# connector_motor.net
KiCad netlist of a schematic drawn in EAGLE
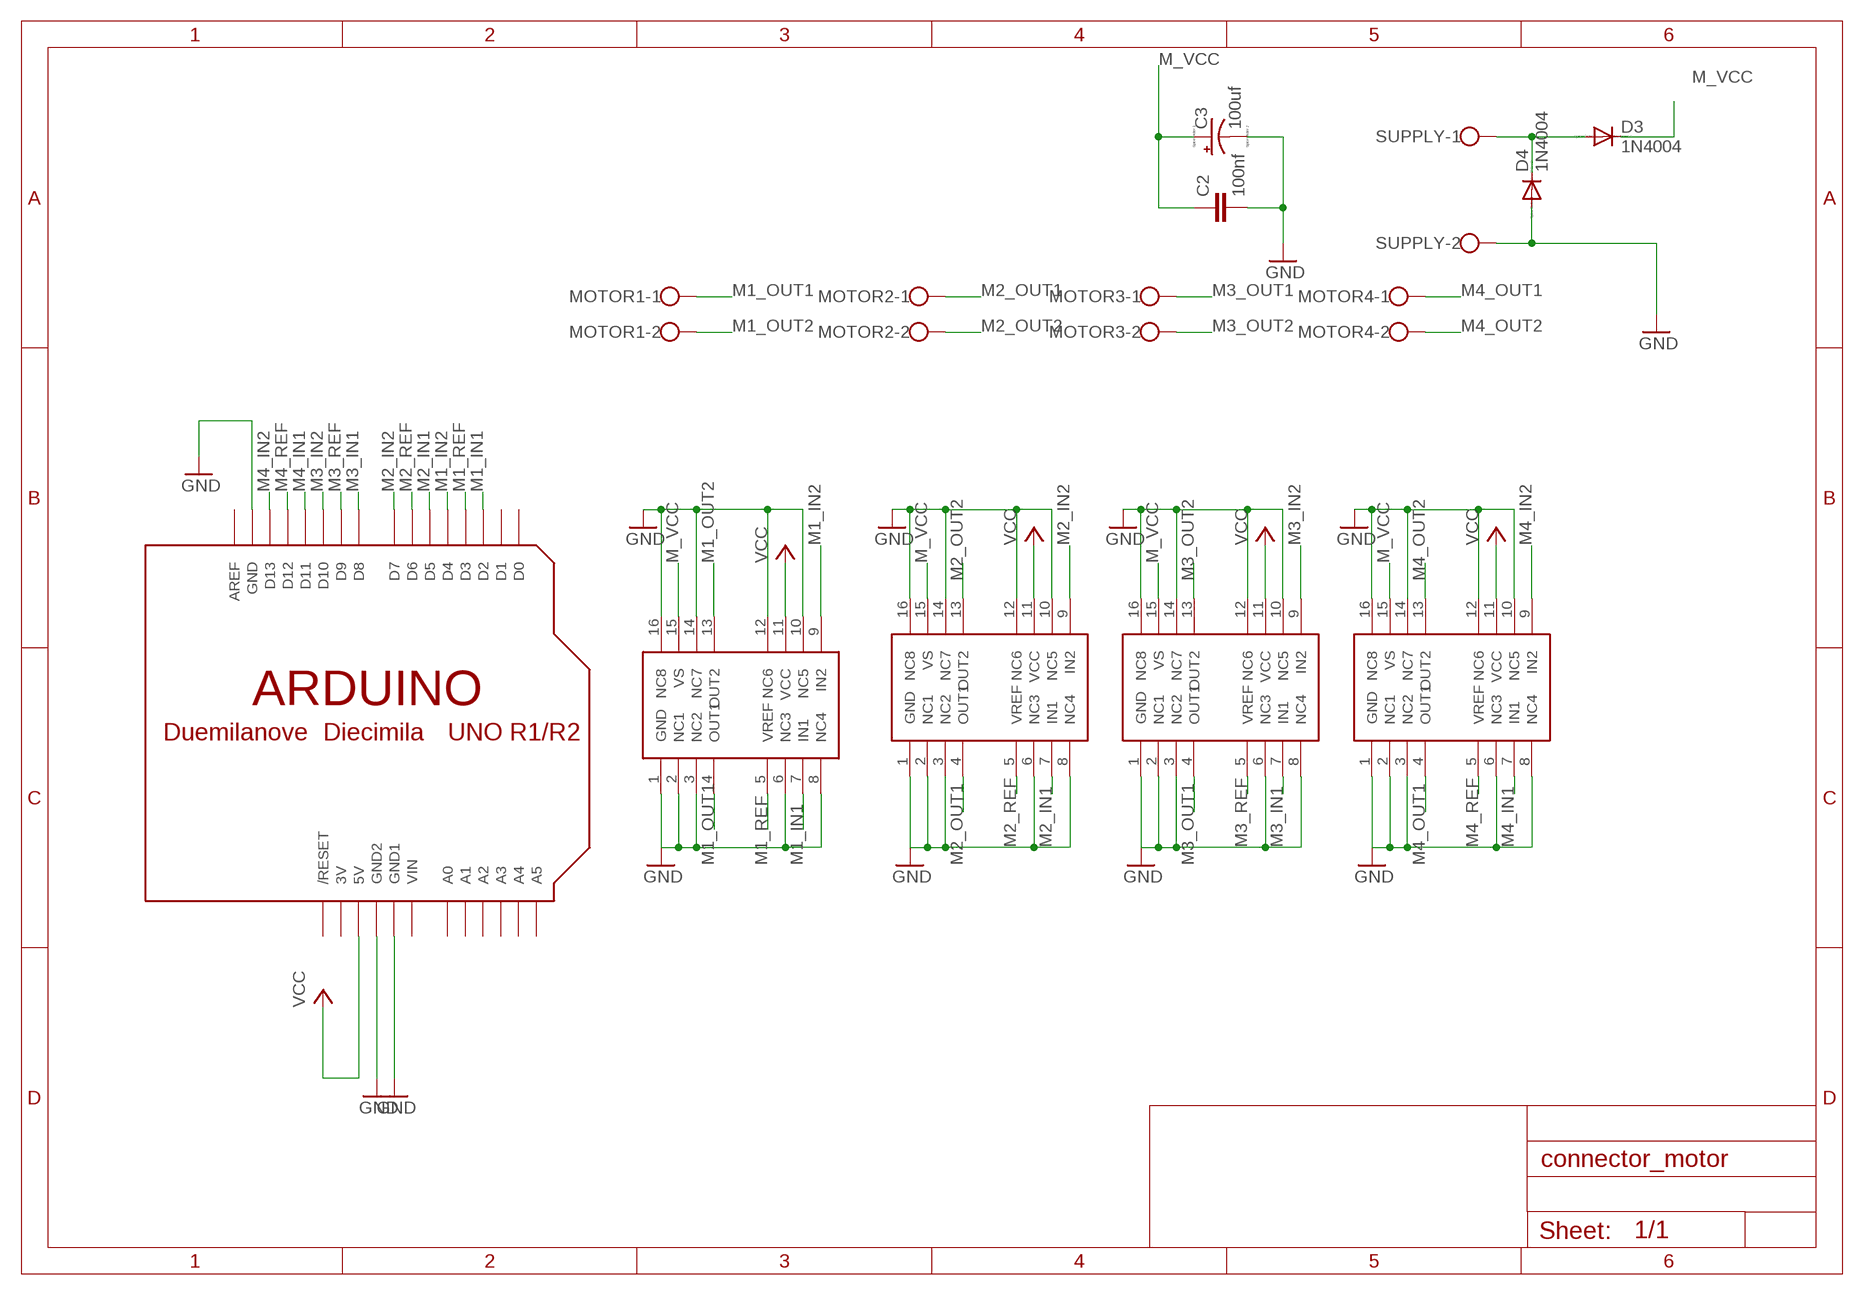
[diagram p0: schematic, sheet 1]

(export (version "E")
  (design (tool "Eeschema 10.0.6"))
  (components
    (comp (ref "C2")
      (value "100nf")
      (footprint "eagle-import:C0603")
      (libsource (lib "eagle-import") (part "C-EUC0603"))
    )
    (comp (ref "C3")
      (value "100uf")
      (footprint "eagle-import:153CLV-0405")
      (libsource (lib "eagle-import") (part "CPOL-US153CLV-0405"))
    )
    (comp (ref "D3")
      (value "1N4004")
      (footprint "eagle-import:DO41-10")
      (libsource (lib "eagle-import") (part "1N4004"))
    )
    (comp (ref "D4")
      (value "1N4004")
      (footprint "eagle-import:DO41-10")
      (libsource (lib "eagle-import") (part "1N4004"))
    )
    (comp (ref "MOTOR1")
      (value "W237-102")
      (footprint "eagle-import:W237-102")
      (fields (field (name "MPN") "237-102"))
      (libsource (lib "eagle-import") (part "W237-102"))
    )
    (comp (ref "MOTOR2")
      (value "W237-102")
      (footprint "eagle-import:W237-102")
      (fields (field (name "MPN") "237-102"))
      (libsource (lib "eagle-import") (part "W237-102"))
    )
    (comp (ref "MOTOR3")
      (value "W237-102")
      (footprint "eagle-import:W237-102")
      (fields (field (name "MPN") "237-102"))
      (libsource (lib "eagle-import") (part "W237-102"))
    )
    (comp (ref "MOTOR4")
      (value "W237-102")
      (footprint "eagle-import:W237-102")
      (fields (field (name "MPN") "237-102"))
      (libsource (lib "eagle-import") (part "W237-102"))
    )
    (comp (ref "SUPPLY")
      (value "W237-102")
      (footprint "eagle-import:W237-102")
      (fields (field (name "MPN") "237-102"))
      (libsource (lib "eagle-import") (part "W237-102"))
    )
    (comp (ref "U$1")
      (value "ARDUINO-NOHOLE")
      (footprint "eagle-import:ARDUINO-NOHOLE")
      (libsource (lib "eagle-import") (part "ARDUINO-NOHOLE"))
    )
    (comp (ref "U$2")
      (value "MOTOR-DRIVER-TA7281FG")
      (footprint "eagle-import:MOTOR-DRIVER-TA7291FG")
      (libsource (lib "eagle-import") (part "MOTOR-DRIVER-TA7281FG"))
    )
    (comp (ref "U$3")
      (value "MOTOR-DRIVER-TA7281FG")
      (footprint "eagle-import:MOTOR-DRIVER-TA7291FG")
      (libsource (lib "eagle-import") (part "MOTOR-DRIVER-TA7281FG"))
    )
    (comp (ref "U$4")
      (value "MOTOR-DRIVER-TA7281FG")
      (footprint "eagle-import:MOTOR-DRIVER-TA7291FG")
      (libsource (lib "eagle-import") (part "MOTOR-DRIVER-TA7281FG"))
    )
    (comp (ref "U$5")
      (value "MOTOR-DRIVER-TA7281FG")
      (footprint "eagle-import:MOTOR-DRIVER-TA7291FG")
      (libsource (lib "eagle-import") (part "MOTOR-DRIVER-TA7281FG"))
    )
  )
  (nets
    (net (code "1") (name "/3V") (class "Default")
      (node (ref "U$1") (pin "3V") (pinfunction "3V_3V") (pintype "power_in"))
    )
    (net (code "2") (name "/M1_IN1") (class "Default")
      (node (ref "U$1") (pin "D2") (pinfunction "D2_D2") (pintype "bidirectional"))
      (node (ref "U$3") (pin "7") (pinfunction "IN1_7") (pintype "bidirectional"))
    )
    (net (code "3") (name "/M1_IN2") (class "Default")
      (node (ref "U$1") (pin "D4") (pinfunction "D4_D4") (pintype "bidirectional"))
      (node (ref "U$3") (pin "9") (pinfunction "IN2_9") (pintype "bidirectional"))
    )
    (net (code "4") (name "/M1_OUT1") (class "Default")
      (node (ref "MOTOR1") (pin "1") (pinfunction "KL_1") (pintype "passive"))
      (node (ref "U$3") (pin "4") (pinfunction "OUT1_4") (pintype "bidirectional"))
    )
    (net (code "5") (name "/M1_OUT2") (class "Default")
      (node (ref "MOTOR1") (pin "2") (pinfunction "KL_2") (pintype "passive"))
      (node (ref "U$3") (pin "13") (pinfunction "OUT2_13") (pintype "bidirectional"))
    )
    (net (code "6") (name "/M1_REF") (class "Default")
      (node (ref "U$1") (pin "D3") (pinfunction "D3_D3") (pintype "bidirectional"))
      (node (ref "U$3") (pin "5") (pinfunction "VREF_5") (pintype "bidirectional"))
    )
    (net (code "7") (name "/M2_IN1") (class "Default")
      (node (ref "U$1") (pin "D5") (pinfunction "D5_D5") (pintype "bidirectional"))
      (node (ref "U$4") (pin "7") (pinfunction "IN1_7") (pintype "bidirectional"))
    )
    (net (code "8") (name "/M2_IN2") (class "Default")
      (node (ref "U$1") (pin "D7") (pinfunction "D7_D7") (pintype "bidirectional"))
      (node (ref "U$4") (pin "9") (pinfunction "IN2_9") (pintype "bidirectional"))
    )
    (net (code "9") (name "/M2_OUT1") (class "Default")
      (node (ref "MOTOR2") (pin "1") (pinfunction "KL_1") (pintype "passive"))
      (node (ref "U$4") (pin "4") (pinfunction "OUT1_4") (pintype "bidirectional"))
    )
    (net (code "10") (name "/M2_OUT2") (class "Default")
      (node (ref "MOTOR2") (pin "2") (pinfunction "KL_2") (pintype "passive"))
      (node (ref "U$4") (pin "13") (pinfunction "OUT2_13") (pintype "bidirectional"))
    )
    (net (code "11") (name "/M2_REF") (class "Default")
      (node (ref "U$1") (pin "D6") (pinfunction "D6_D6") (pintype "bidirectional"))
      (node (ref "U$4") (pin "5") (pinfunction "VREF_5") (pintype "bidirectional"))
    )
    (net (code "12") (name "/M3_IN1") (class "Default")
      (node (ref "U$1") (pin "D8") (pinfunction "D8_D8") (pintype "bidirectional"))
      (node (ref "U$2") (pin "7") (pinfunction "IN1_7") (pintype "bidirectional"))
    )
    (net (code "13") (name "/M3_IN2") (class "Default")
      (node (ref "U$1") (pin "D10") (pinfunction "D10_D10") (pintype "bidirectional"))
      (node (ref "U$2") (pin "9") (pinfunction "IN2_9") (pintype "bidirectional"))
    )
    (net (code "14") (name "/M3_OUT1") (class "Default")
      (node (ref "MOTOR3") (pin "1") (pinfunction "KL_1") (pintype "passive"))
      (node (ref "U$2") (pin "4") (pinfunction "OUT1_4") (pintype "bidirectional"))
    )
    (net (code "15") (name "/M3_OUT2") (class "Default")
      (node (ref "MOTOR3") (pin "2") (pinfunction "KL_2") (pintype "passive"))
      (node (ref "U$2") (pin "13") (pinfunction "OUT2_13") (pintype "bidirectional"))
    )
    (net (code "16") (name "/M3_REF") (class "Default")
      (node (ref "U$1") (pin "D9") (pinfunction "D9_D9") (pintype "bidirectional"))
      (node (ref "U$2") (pin "5") (pinfunction "VREF_5") (pintype "bidirectional"))
    )
    (net (code "17") (name "/M4_IN1") (class "Default")
      (node (ref "U$1") (pin "D11") (pinfunction "D11_D11") (pintype "bidirectional"))
      (node (ref "U$5") (pin "7") (pinfunction "IN1_7") (pintype "bidirectional"))
    )
    (net (code "18") (name "/M4_IN2") (class "Default")
      (node (ref "U$1") (pin "D13") (pinfunction "D13_D13") (pintype "bidirectional"))
      (node (ref "U$5") (pin "9") (pinfunction "IN2_9") (pintype "bidirectional"))
    )
    (net (code "19") (name "/M4_OUT1") (class "Default")
      (node (ref "MOTOR4") (pin "1") (pinfunction "KL_1") (pintype "passive"))
      (node (ref "U$5") (pin "4") (pinfunction "OUT1_4") (pintype "bidirectional"))
    )
    (net (code "20") (name "/M4_OUT2") (class "Default")
      (node (ref "MOTOR4") (pin "2") (pinfunction "KL_2") (pintype "passive"))
      (node (ref "U$5") (pin "13") (pinfunction "OUT2_13") (pintype "bidirectional"))
    )
    (net (code "21") (name "/M4_REF") (class "Default")
      (node (ref "U$1") (pin "D12") (pinfunction "D12_D12") (pintype "bidirectional"))
      (node (ref "U$5") (pin "5") (pinfunction "VREF_5") (pintype "bidirectional"))
    )
    (net (code "22") (name "/M_VCC") (class "Default")
      (node (ref "C2") (pin "1") (pinfunction "1_1") (pintype "passive"))
      (node (ref "C3") (pin "+") (pinfunction "+_+") (pintype "passive"))
      (node (ref "D3") (pin "C") (pinfunction "C_C") (pintype "passive"))
      (node (ref "U$2") (pin "15") (pinfunction "VS_15") (pintype "bidirectional"))
      (node (ref "U$3") (pin "15") (pinfunction "VS_15") (pintype "bidirectional"))
      (node (ref "U$4") (pin "15") (pinfunction "VS_15") (pintype "bidirectional"))
      (node (ref "U$5") (pin "15") (pinfunction "VS_15") (pintype "bidirectional"))
    )
    (net (code "23") (name "/VIN") (class "Default")
      (node (ref "U$1") (pin "VIN") (pinfunction "VIN_VIN") (pintype "power_in"))
    )
    (net (code "24") (name "GND") (class "Default")
      (node (ref "C2") (pin "2") (pinfunction "2_2") (pintype "passive"))
      (node (ref "C3") (pin "-") (pinfunction "-_-") (pintype "passive"))
      (node (ref "D4") (pin "A") (pinfunction "A_A") (pintype "passive"))
      (node (ref "SUPPLY") (pin "2") (pinfunction "KL_2") (pintype "passive"))
      (node (ref "U$1") (pin "GND") (pinfunction "GND_GND") (pintype "power_in"))
      (node (ref "U$1") (pin "GND1") (pinfunction "GND1_GND1") (pintype "power_in"))
      (node (ref "U$1") (pin "GND2") (pinfunction "GND2_GND2") (pintype "power_in"))
      (node (ref "U$2") (pin "1") (pinfunction "GND_1") (pintype "bidirectional"))
      (node (ref "U$2") (pin "10") (pinfunction "NC5_10") (pintype "bidirectional"))
      (node (ref "U$2") (pin "12") (pinfunction "NC6_12") (pintype "bidirectional"))
      (node (ref "U$2") (pin "14") (pinfunction "NC7_14") (pintype "bidirectional"))
      (node (ref "U$2") (pin "16") (pinfunction "NC8_16") (pintype "bidirectional"))
      (node (ref "U$2") (pin "2") (pinfunction "NC1_2") (pintype "bidirectional"))
      (node (ref "U$2") (pin "3") (pinfunction "NC2_3") (pintype "bidirectional"))
      (node (ref "U$2") (pin "6") (pinfunction "NC3_6") (pintype "bidirectional"))
      (node (ref "U$2") (pin "8") (pinfunction "NC4_8") (pintype "bidirectional"))
      (node (ref "U$3") (pin "1") (pinfunction "GND_1") (pintype "bidirectional"))
      (node (ref "U$3") (pin "10") (pinfunction "NC5_10") (pintype "bidirectional"))
      (node (ref "U$3") (pin "12") (pinfunction "NC6_12") (pintype "bidirectional"))
      (node (ref "U$3") (pin "14") (pinfunction "NC7_14") (pintype "bidirectional"))
      (node (ref "U$3") (pin "16") (pinfunction "NC8_16") (pintype "bidirectional"))
      (node (ref "U$3") (pin "2") (pinfunction "NC1_2") (pintype "bidirectional"))
      (node (ref "U$3") (pin "3") (pinfunction "NC2_3") (pintype "bidirectional"))
      (node (ref "U$3") (pin "6") (pinfunction "NC3_6") (pintype "bidirectional"))
      (node (ref "U$3") (pin "8") (pinfunction "NC4_8") (pintype "bidirectional"))
      (node (ref "U$4") (pin "1") (pinfunction "GND_1") (pintype "bidirectional"))
      (node (ref "U$4") (pin "10") (pinfunction "NC5_10") (pintype "bidirectional"))
      (node (ref "U$4") (pin "12") (pinfunction "NC6_12") (pintype "bidirectional"))
      (node (ref "U$4") (pin "14") (pinfunction "NC7_14") (pintype "bidirectional"))
      (node (ref "U$4") (pin "16") (pinfunction "NC8_16") (pintype "bidirectional"))
      (node (ref "U$4") (pin "2") (pinfunction "NC1_2") (pintype "bidirectional"))
      (node (ref "U$4") (pin "3") (pinfunction "NC2_3") (pintype "bidirectional"))
      (node (ref "U$4") (pin "6") (pinfunction "NC3_6") (pintype "bidirectional"))
      (node (ref "U$4") (pin "8") (pinfunction "NC4_8") (pintype "bidirectional"))
      (node (ref "U$5") (pin "1") (pinfunction "GND_1") (pintype "bidirectional"))
      (node (ref "U$5") (pin "10") (pinfunction "NC5_10") (pintype "bidirectional"))
      (node (ref "U$5") (pin "12") (pinfunction "NC6_12") (pintype "bidirectional"))
      (node (ref "U$5") (pin "14") (pinfunction "NC7_14") (pintype "bidirectional"))
      (node (ref "U$5") (pin "16") (pinfunction "NC8_16") (pintype "bidirectional"))
      (node (ref "U$5") (pin "2") (pinfunction "NC1_2") (pintype "bidirectional"))
      (node (ref "U$5") (pin "3") (pinfunction "NC2_3") (pintype "bidirectional"))
      (node (ref "U$5") (pin "6") (pinfunction "NC3_6") (pintype "bidirectional"))
      (node (ref "U$5") (pin "8") (pinfunction "NC4_8") (pintype "bidirectional"))
    )
    (net (code "25") (name "Net-(SUPPLYA-KL)") (class "Default")
      (node (ref "D3") (pin "A") (pinfunction "A_A") (pintype "passive"))
      (node (ref "D4") (pin "C") (pinfunction "C_C") (pintype "passive"))
      (node (ref "SUPPLY") (pin "1") (pinfunction "KL_1") (pintype "passive"))
    )
    (net (code "26") (name "VCC") (class "Default")
      (node (ref "U$1") (pin "5V") (pinfunction "5V_5V") (pintype "power_in"))
      (node (ref "U$2") (pin "11") (pinfunction "VCC_11") (pintype "bidirectional"))
      (node (ref "U$3") (pin "11") (pinfunction "VCC_11") (pintype "bidirectional"))
      (node (ref "U$4") (pin "11") (pinfunction "VCC_11") (pintype "bidirectional"))
      (node (ref "U$5") (pin "11") (pinfunction "VCC_11") (pintype "bidirectional"))
    )
    (net (code "27") (name "unconnected-(U$1-PadA0)") (class "Default")
      (node (ref "U$1") (pin "A0") (pinfunction "A0_A0") (pintype "bidirectional"))
    )
    (net (code "28") (name "unconnected-(U$1-PadA1)") (class "Default")
      (node (ref "U$1") (pin "A1") (pinfunction "A1_A1") (pintype "bidirectional"))
    )
    (net (code "29") (name "unconnected-(U$1-PadA2)") (class "Default")
      (node (ref "U$1") (pin "A2") (pinfunction "A2_A2") (pintype "bidirectional"))
    )
    (net (code "30") (name "unconnected-(U$1-PadA3)") (class "Default")
      (node (ref "U$1") (pin "A3") (pinfunction "A3_A3") (pintype "bidirectional"))
    )
    (net (code "31") (name "unconnected-(U$1-PadA4)") (class "Default")
      (node (ref "U$1") (pin "A4") (pinfunction "A4_A4") (pintype "bidirectional"))
    )
    (net (code "32") (name "unconnected-(U$1-PadA5)") (class "Default")
      (node (ref "U$1") (pin "A5") (pinfunction "A5_A5") (pintype "bidirectional"))
    )
    (net (code "33") (name "unconnected-(U$1-PadAREF)") (class "Default")
      (node (ref "U$1") (pin "AREF") (pinfunction "AREF_AREF") (pintype "bidirectional"))
    )
    (net (code "34") (name "unconnected-(U$1-PadD0)") (class "Default")
      (node (ref "U$1") (pin "D0") (pinfunction "D0_D0") (pintype "bidirectional"))
    )
    (net (code "35") (name "unconnected-(U$1-PadD1)") (class "Default")
      (node (ref "U$1") (pin "D1") (pinfunction "D1_D1") (pintype "bidirectional"))
    )
    (net (code "36") (name "unconnected-(U$1-{slash}RESET-PadRESET)") (class "Default")
      (node (ref "U$1") (pin "RESET") (pinfunction "/RESET_RESET") (pintype "bidirectional"))
    )
  )
)
